# amiketo.net
KiCad netlist of a schematic drawn in EAGLE
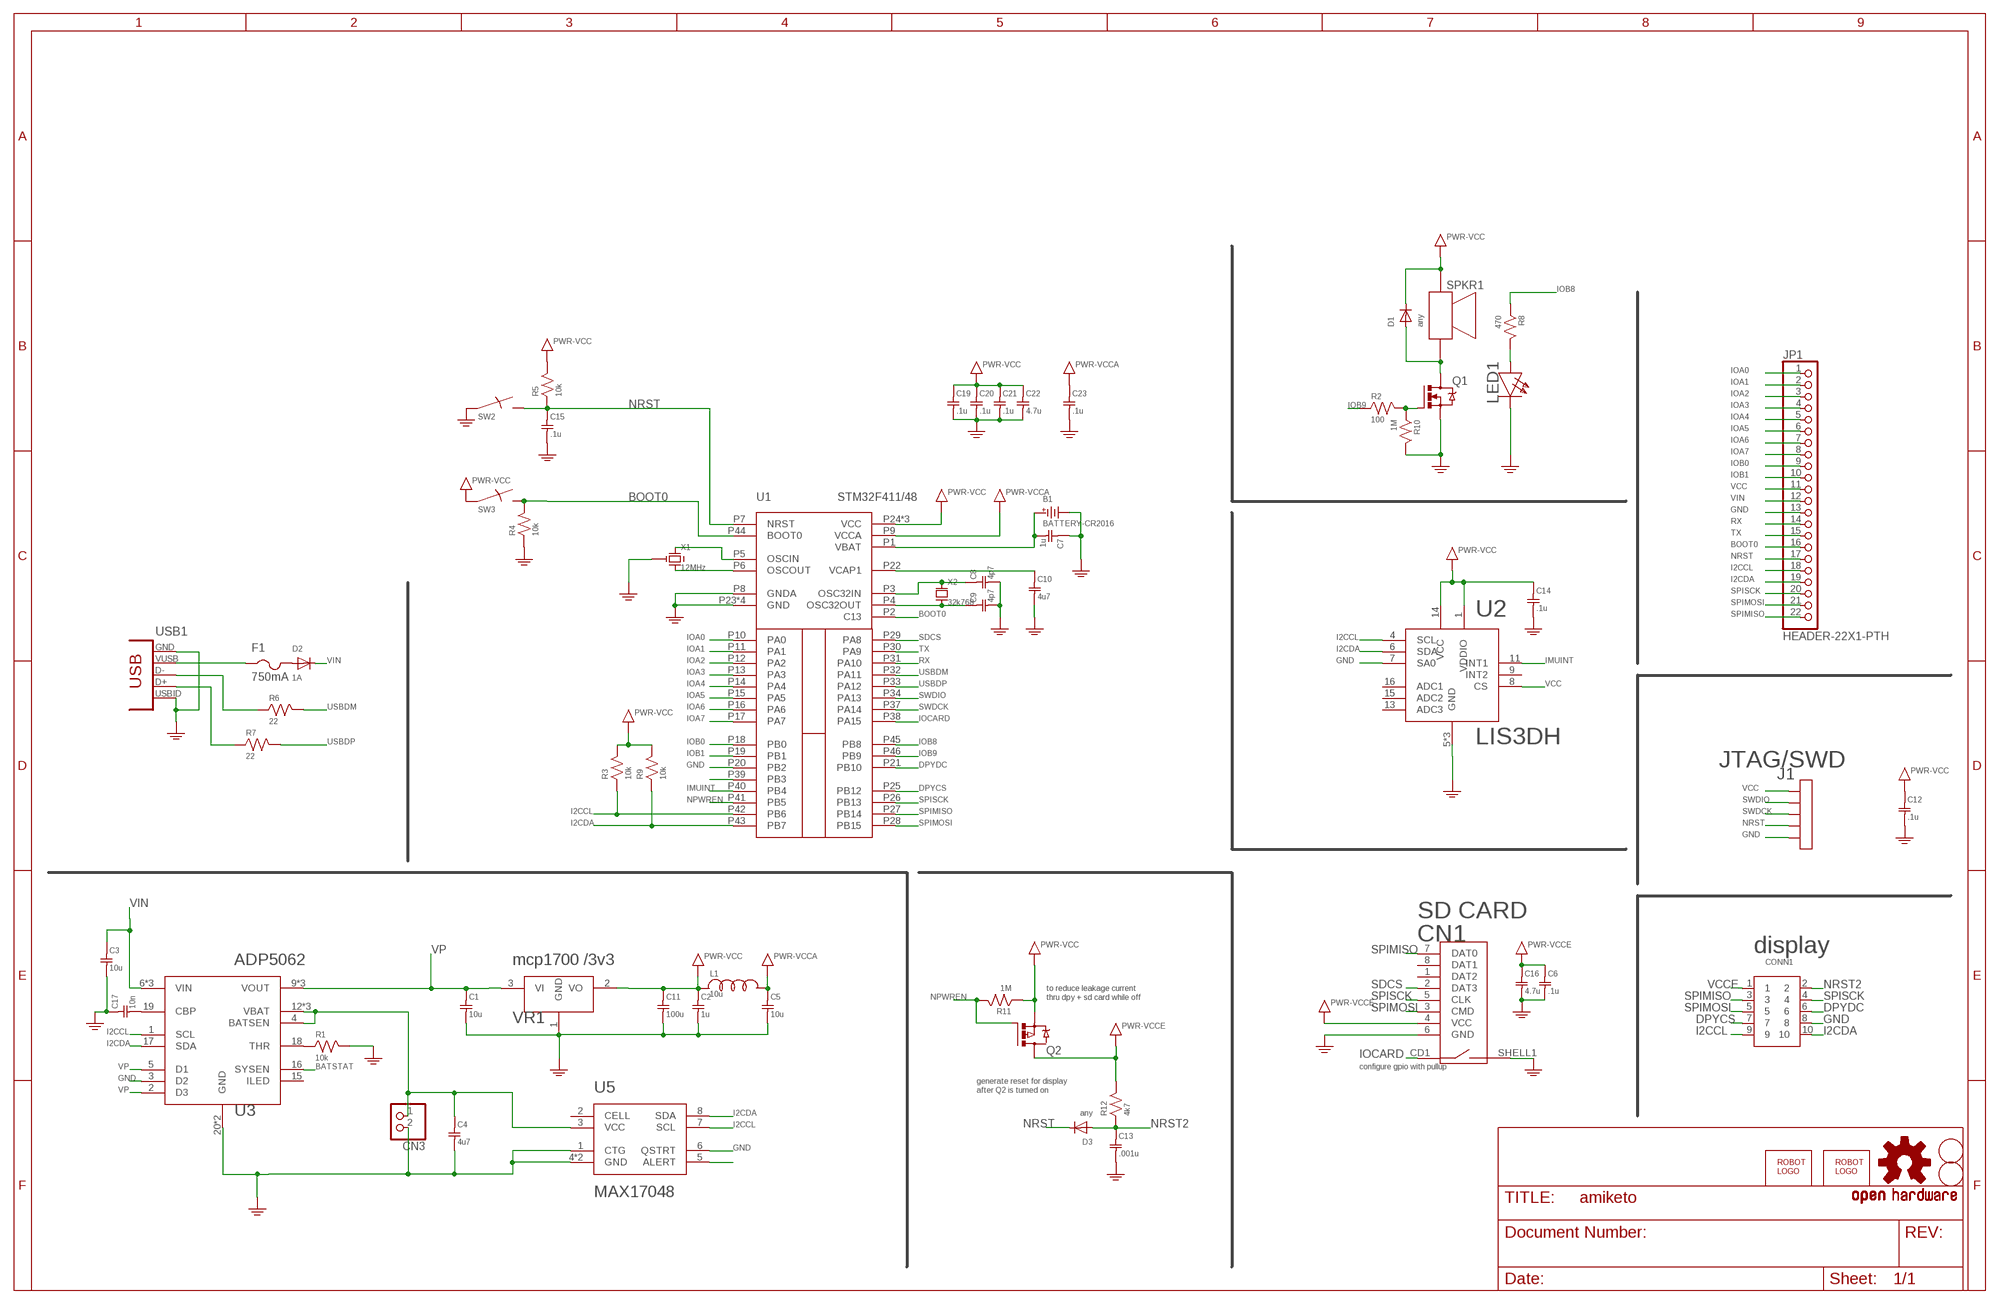
[diagram p0: schematic, sheet 1]

(export (version "E")
  (design (tool "Eeschema 10.0.6"))
  (components
    (comp (ref "B1")
      (value "BATTERY-CR2016")
      (footprint "eagle-import:CR1216")
      (libsource (lib "eagle-import") (part "BATTERY-CR2016"))
    )
    (comp (ref "C1")
      (value "10u")
      (footprint "eagle-import:SMD0603")
      (libsource (lib "eagle-import") (part "C0603"))
    )
    (comp (ref "C2")
      (value "1u")
      (footprint "eagle-import:SMD0603")
      (libsource (lib "eagle-import") (part "C0603"))
    )
    (comp (ref "C3")
      (value "10u")
      (footprint "eagle-import:SMD0603")
      (libsource (lib "eagle-import") (part "C0603"))
    )
    (comp (ref "C4")
      (value "4u7")
      (footprint "eagle-import:SMD0603")
      (libsource (lib "eagle-import") (part "C0603"))
    )
    (comp (ref "C5")
      (value "10u")
      (footprint "eagle-import:SMD0603")
      (libsource (lib "eagle-import") (part "C0603"))
    )
    (comp (ref "C6")
      (value ".1u")
      (footprint "eagle-import:SMD0603")
      (libsource (lib "eagle-import") (part "C0603"))
    )
    (comp (ref "C7")
      (value "1u")
      (footprint "eagle-import:SMD0603")
      (libsource (lib "eagle-import") (part "C0603"))
    )
    (comp (ref "C8")
      (value "4p7")
      (footprint "eagle-import:SMD0603")
      (libsource (lib "eagle-import") (part "C0603"))
    )
    (comp (ref "C9")
      (value "4p7")
      (footprint "eagle-import:SMD0603")
      (libsource (lib "eagle-import") (part "C0603"))
    )
    (comp (ref "C10")
      (value "4u7")
      (footprint "eagle-import:SMD0603")
      (libsource (lib "eagle-import") (part "C0603"))
    )
    (comp (ref "C11")
      (value "100u")
      (footprint "eagle-import:SMD1210")
      (libsource (lib "eagle-import") (part "C1210"))
    )
    (comp (ref "C12")
      (value ".1u")
      (footprint "eagle-import:SMD0603")
      (libsource (lib "eagle-import") (part "C0603"))
    )
    (comp (ref "C13")
      (value ".001u")
      (footprint "eagle-import:SMD0603")
      (libsource (lib "eagle-import") (part "C0603"))
    )
    (comp (ref "C14")
      (value ".1u")
      (footprint "eagle-import:SMD0603")
      (libsource (lib "eagle-import") (part "C0603"))
    )
    (comp (ref "C15")
      (value ".1u")
      (footprint "eagle-import:SMD0603")
      (libsource (lib "eagle-import") (part "C0603"))
    )
    (comp (ref "C16")
      (value "4.7u")
      (footprint "eagle-import:SMD0603")
      (libsource (lib "eagle-import") (part "C0603"))
    )
    (comp (ref "C17")
      (value "10n")
      (footprint "eagle-import:SMD0603")
      (libsource (lib "eagle-import") (part "C0603"))
    )
    (comp (ref "C19")
      (value ".1u")
      (footprint "eagle-import:SMD0603")
      (libsource (lib "eagle-import") (part "C0603"))
    )
    (comp (ref "C20")
      (value ".1u")
      (footprint "eagle-import:SMD0603")
      (libsource (lib "eagle-import") (part "C0603"))
    )
    (comp (ref "C21")
      (value ".1u")
      (footprint "eagle-import:SMD0603")
      (libsource (lib "eagle-import") (part "C0603"))
    )
    (comp (ref "C22")
      (value "4.7u")
      (footprint "eagle-import:SMD0603")
      (libsource (lib "eagle-import") (part "C0603"))
    )
    (comp (ref "C23")
      (value ".1u")
      (footprint "eagle-import:SMD0603")
      (libsource (lib "eagle-import") (part "C0603"))
    )
    (comp (ref "CN1")
      (value "MICROSD-EJECT")
      (footprint "eagle-import:MICROSD_EJECTOR")
      (libsource (lib "eagle-import") (part "MICROSD-EJECT"))
    )
    (comp (ref "CN3")
      (value "JST_2PIN-SMT-RA")
      (footprint "eagle-import:JST-PH-2-SMT-RA")
      (libsource (lib "eagle-import") (part "JST_2PIN-SMT-RA"))
    )
    (comp (ref "CONN1")
      (value "HEADER-5X2-PTH")
      (footprint "eagle-import:HEADER-5X2-PTH")
      (libsource (lib "eagle-import") (part "HEADER-5X2-PTH"))
    )
    (comp (ref "D1")
      (value "any")
      (footprint "eagle-import:SOD-323")
      (libsource (lib "eagle-import") (part "DIODESOD-323"))
    )
    (comp (ref "D2")
      (value "1A")
      (footprint "eagle-import:SMD0805D")
      (libsource (lib "eagle-import") (part "DIODE-0805"))
    )
    (comp (ref "D3")
      (value "any")
      (footprint "eagle-import:SOD-323")
      (libsource (lib "eagle-import") (part "DIODESOD-323"))
    )
    (comp (ref "F1")
      (value "750mA")
      (footprint "eagle-import:SMD1206")
      (libsource (lib "eagle-import") (part "FUSE"))
    )
    (comp (ref "J1")
      (value "HEADER-5X1")
      (footprint "eagle-import:HEADER-5X1-SMD127-NOCR")
      (libsource (lib "eagle-import") (part "HEADER-5X1"))
    )
    (comp (ref "JP1")
      (value "HEADER-22X1-PTH")
      (footprint "eagle-import:HEADER-22X1-PTH")
      (libsource (lib "eagle-import") (part "HEADER-22X1-PTH"))
    )
    (comp (ref "L1")
      (value "10u")
      (footprint "eagle-import:SMD0603")
      (libsource (lib "eagle-import") (part "LSMD0603"))
    )
    (comp (ref "LED1")
      (value "white")
      (footprint "eagle-import:SMD0603D")
      (libsource (lib "eagle-import") (part "LED"))
    )
    (comp (ref "LOGO1")
      (value "OSHW-LOGOM")
      (footprint "eagle-import:OSHW-LOGO-M")
      (libsource (lib "eagle-import") (part "OSHW-LOGOM"))
    )
    (comp (ref "Q1")
      (value "IRLML6344TRPBF")
      (footprint "eagle-import:SOT-23")
      (libsource (lib "eagle-import") (part "MOSFETSOT-23"))
    )
    (comp (ref "Q2")
      (value "DMP2035U-7")
      (footprint "eagle-import:SOT-23")
      (libsource (lib "eagle-import") (part "MOSFET-P"))
    )
    (comp (ref "R1")
      (value "10k")
      (footprint "eagle-import:SMD0603")
      (libsource (lib "eagle-import") (part "R0603"))
    )
    (comp (ref "R2")
      (value "100")
      (footprint "eagle-import:SMD0603")
      (libsource (lib "eagle-import") (part "R0603"))
    )
    (comp (ref "R3")
      (value "10k")
      (footprint "eagle-import:SMD0603")
      (libsource (lib "eagle-import") (part "R0603"))
    )
    (comp (ref "R4")
      (value "10k")
      (footprint "eagle-import:SMD0603")
      (libsource (lib "eagle-import") (part "R0603"))
    )
    (comp (ref "R5")
      (value "10k")
      (footprint "eagle-import:SMD0603")
      (libsource (lib "eagle-import") (part "R0603"))
    )
    (comp (ref "R6")
      (value "22")
      (footprint "eagle-import:SMD0603")
      (libsource (lib "eagle-import") (part "R0603"))
    )
    (comp (ref "R7")
      (value "22")
      (footprint "eagle-import:SMD0603")
      (libsource (lib "eagle-import") (part "R0603"))
    )
    (comp (ref "R8")
      (value "470")
      (footprint "eagle-import:SMD0603")
      (libsource (lib "eagle-import") (part "R0603"))
    )
    (comp (ref "R9")
      (value "10k")
      (footprint "eagle-import:SMD0603")
      (libsource (lib "eagle-import") (part "R0603"))
    )
    (comp (ref "R10")
      (value "1M")
      (footprint "eagle-import:SMD0603")
      (libsource (lib "eagle-import") (part "R0603"))
    )
    (comp (ref "R11")
      (value "1M")
      (footprint "eagle-import:SMD0603")
      (libsource (lib "eagle-import") (part "R0603"))
    )
    (comp (ref "R12")
      (value "4k7")
      (footprint "eagle-import:SMD0603")
      (libsource (lib "eagle-import") (part "R0603"))
    )
    (comp (ref "SPKR1")
      (value "PUI-5040")
      (footprint "eagle-import:PUI-0540")
      (libsource (lib "eagle-import") (part "PUI-5040"))
    )
    (comp (ref "SW2")
      (value "SWITCHKMR211")
      (footprint "eagle-import:KMR211")
      (libsource (lib "eagle-import") (part "SWITCHKMR211"))
    )
    (comp (ref "SW3")
      (value "SWITCHKMR211")
      (footprint "eagle-import:KMR211")
      (libsource (lib "eagle-import") (part "SWITCHKMR211"))
    )
    (comp (ref "U$1")
      (value "ROBOTMAN-LOGO2")
      (footprint "eagle-import:ROBOTMAN-LOGO2")
      (libsource (lib "eagle-import") (part "ROBOTMAN-LOGO2"))
    )
    (comp (ref "U$2")
      (value "FIDUCIAL")
      (footprint "eagle-import:FIDUCIAL_1MM")
      (libsource (lib "eagle-import") (part "FIDUCIAL"))
    )
    (comp (ref "U$3")
      (value "FIDUCIAL")
      (footprint "eagle-import:FIDUCIAL_1MM")
      (libsource (lib "eagle-import") (part "FIDUCIAL"))
    )
    (comp (ref "U$4")
      (value "ROBOTMAN-LOGO2")
      (footprint "eagle-import:ROBOTMAN-LOGO2")
      (libsource (lib "eagle-import") (part "ROBOTMAN-LOGO2"))
    )
    (comp (ref "U1")
      (value "STM32F411/48")
      (footprint "eagle-import:UQPFN48")
      (libsource (lib "eagle-import") (part "STM32F411/48"))
    )
    (comp (ref "U2")
      (value "LIS3DH")
      (footprint "eagle-import:LGA16A")
      (libsource (lib "eagle-import") (part "LIS3DH"))
    )
    (comp (ref "U3")
      (value "ADP5062")
      (footprint "eagle-import:LGA20P")
      (libsource (lib "eagle-import") (part "ADP5062"))
    )
    (comp (ref "U5")
      (value "MAX17048")
      (footprint "eagle-import:TDFN8EP")
      (libsource (lib "eagle-import") (part "MAX17048"))
    )
    (comp (ref "USB1")
      (value "CON-USB-F-MICRO-B")
      (footprint "eagle-import:CONN_USB_MICRO-B")
      (libsource (lib "eagle-import") (part "CON-USB-F-MICRO-B"))
    )
    (comp (ref "VR1")
      (value "mcp1700 /3v3")
      (footprint "eagle-import:SOT-23-3")
      (libsource (lib "eagle-import") (part "REGULATOR-SOT23-3"))
    )
    (comp (ref "X1")
      (value "12MHz")
      (footprint "eagle-import:RESONATOR-CSTCE")
      (libsource (lib "eagle-import") (part "RESONATORCTCE"))
    )
    (comp (ref "X2")
      (value "32k768")
      (footprint "eagle-import:XTAL-32X15")
      (libsource (lib "eagle-import") (part "XTAL32X15"))
    )
  )
  (nets
    (net (code "1") (name "/BATSTAT") (class "Default")
      (node (ref "U3") (pin "16") (pinfunction "SYSEN_16") (pintype "bidirectional"))
    )
    (net (code "2") (name "/BOOT0") (class "Default")
      (node (ref "JP1") (pin "16") (pinfunction "16_16") (pintype "passive"))
      (node (ref "R4") (pin "2") (pinfunction "P$2_2") (pintype "passive"))
      (node (ref "SW3") (pin "2") (pinfunction "P$2_2") (pintype "passive"))
      (node (ref "SW3") (pin "4") (pinfunction "P$2_4") (pintype "passive"))
      (node (ref "U1") (pin "P2") (pinfunction "C13_P2") (pintype "bidirectional"))
      (node (ref "U1") (pin "P44") (pinfunction "BOOT0_P44") (pintype "bidirectional"))
    )
    (net (code "3") (name "/DPYCS") (class "Default")
      (node (ref "CONN1") (pin "7") (pinfunction "7_7") (pintype "passive"))
      (node (ref "U1") (pin "P25") (pinfunction "PB12_P25") (pintype "bidirectional"))
    )
    (net (code "4") (name "/DPYDC") (class "Default")
      (node (ref "CONN1") (pin "6") (pinfunction "6_6") (pintype "passive"))
      (node (ref "U1") (pin "P21") (pinfunction "PB10_P21") (pintype "bidirectional"))
    )
    (net (code "5") (name "/I2CCL") (class "Default")
      (node (ref "CONN1") (pin "9") (pinfunction "9_9") (pintype "passive"))
      (node (ref "JP1") (pin "18") (pinfunction "18_18") (pintype "passive"))
      (node (ref "R3") (pin "1") (pinfunction "P$1_1") (pintype "passive"))
      (node (ref "U1") (pin "P42") (pinfunction "PB6_P42") (pintype "bidirectional"))
      (node (ref "U2") (pin "4") (pinfunction "SCL_4") (pintype "bidirectional"))
      (node (ref "U3") (pin "1") (pinfunction "SCL_1") (pintype "bidirectional"))
      (node (ref "U5") (pin "7") (pinfunction "SCL_7") (pintype "bidirectional"))
    )
    (net (code "6") (name "/I2CDA") (class "Default")
      (node (ref "CONN1") (pin "10") (pinfunction "10_10") (pintype "passive"))
      (node (ref "JP1") (pin "19") (pinfunction "19_19") (pintype "passive"))
      (node (ref "R9") (pin "1") (pinfunction "P$1_1") (pintype "passive"))
      (node (ref "U1") (pin "P43") (pinfunction "PB7_P43") (pintype "bidirectional"))
      (node (ref "U2") (pin "6") (pinfunction "SDA_6") (pintype "bidirectional"))
      (node (ref "U3") (pin "17") (pinfunction "SDA_17") (pintype "bidirectional"))
      (node (ref "U5") (pin "8") (pinfunction "SDA_8") (pintype "bidirectional"))
    )
    (net (code "7") (name "/IMUINT") (class "Default")
      (node (ref "U1") (pin "P40") (pinfunction "PB4_P40") (pintype "bidirectional"))
      (node (ref "U2") (pin "11") (pinfunction "INT1_11") (pintype "bidirectional"))
    )
    (net (code "8") (name "/IOA0") (class "Default")
      (node (ref "JP1") (pin "1") (pinfunction "1_1") (pintype "passive"))
      (node (ref "U1") (pin "P10") (pinfunction "PA0_P10") (pintype "bidirectional"))
    )
    (net (code "9") (name "/IOA1") (class "Default")
      (node (ref "JP1") (pin "2") (pinfunction "2_2") (pintype "passive"))
      (node (ref "U1") (pin "P11") (pinfunction "PA1_P11") (pintype "bidirectional"))
    )
    (net (code "10") (name "/IOA2") (class "Default")
      (node (ref "JP1") (pin "3") (pinfunction "3_3") (pintype "passive"))
      (node (ref "U1") (pin "P12") (pinfunction "PA2_P12") (pintype "bidirectional"))
    )
    (net (code "11") (name "/IOA3") (class "Default")
      (node (ref "JP1") (pin "4") (pinfunction "4_4") (pintype "passive"))
      (node (ref "U1") (pin "P13") (pinfunction "PA3_P13") (pintype "bidirectional"))
    )
    (net (code "12") (name "/IOA4") (class "Default")
      (node (ref "JP1") (pin "5") (pinfunction "5_5") (pintype "passive"))
      (node (ref "U1") (pin "P14") (pinfunction "PA4_P14") (pintype "bidirectional"))
    )
    (net (code "13") (name "/IOA5") (class "Default")
      (node (ref "JP1") (pin "6") (pinfunction "6_6") (pintype "passive"))
      (node (ref "U1") (pin "P15") (pinfunction "PA5_P15") (pintype "bidirectional"))
    )
    (net (code "14") (name "/IOA6") (class "Default")
      (node (ref "JP1") (pin "7") (pinfunction "7_7") (pintype "passive"))
      (node (ref "U1") (pin "P16") (pinfunction "PA6_P16") (pintype "bidirectional"))
    )
    (net (code "15") (name "/IOA7") (class "Default")
      (node (ref "JP1") (pin "8") (pinfunction "8_8") (pintype "passive"))
      (node (ref "U1") (pin "P17") (pinfunction "PA7_P17") (pintype "bidirectional"))
    )
    (net (code "16") (name "/IOB0") (class "Default")
      (node (ref "JP1") (pin "9") (pinfunction "9_9") (pintype "passive"))
      (node (ref "U1") (pin "P18") (pinfunction "PB0_P18") (pintype "bidirectional"))
    )
    (net (code "17") (name "/IOB1") (class "Default")
      (node (ref "JP1") (pin "10") (pinfunction "10_10") (pintype "passive"))
      (node (ref "U1") (pin "P19") (pinfunction "PB1_P19") (pintype "bidirectional"))
    )
    (net (code "18") (name "/IOB8") (class "Default")
      (node (ref "R8") (pin "1") (pinfunction "P$1_1") (pintype "passive"))
      (node (ref "U1") (pin "P45") (pinfunction "PB8_P45") (pintype "bidirectional"))
    )
    (net (code "19") (name "/IOB9") (class "Default")
      (node (ref "R2") (pin "1") (pinfunction "P$1_1") (pintype "passive"))
      (node (ref "U1") (pin "P46") (pinfunction "PB9_P46") (pintype "bidirectional"))
    )
    (net (code "20") (name "/IOCARD") (class "Default")
      (node (ref "CN1") (pin "CD1") (pinfunction "SW1_CD1") (pintype "bidirectional"))
      (node (ref "U1") (pin "P38") (pinfunction "PA15_P38") (pintype "bidirectional"))
    )
    (net (code "21") (name "/NPWREN") (class "Default")
      (node (ref "Q2") (pin "1") (pinfunction "G_1") (pintype "passive"))
      (node (ref "R11") (pin "2") (pinfunction "P$2_2") (pintype "passive"))
      (node (ref "U1") (pin "P41") (pinfunction "PB5_P41") (pintype "bidirectional"))
    )
    (net (code "22") (name "/NRST") (class "Default")
      (node (ref "C15") (pin "1") (pinfunction "P$1_1") (pintype "passive"))
      (node (ref "D3") (pin "C") (pinfunction "C_C") (pintype "passive"))
      (node (ref "J1") (pin "P$4") (pinfunction "4_P$4") (pintype "bidirectional"))
      (node (ref "JP1") (pin "17") (pinfunction "17_17") (pintype "passive"))
      (node (ref "R5") (pin "1") (pinfunction "P$1_1") (pintype "passive"))
      (node (ref "SW2") (pin "2") (pinfunction "P$2_2") (pintype "passive"))
      (node (ref "SW2") (pin "4") (pinfunction "P$2_4") (pintype "passive"))
      (node (ref "U1") (pin "P7") (pinfunction "NRST_P7") (pintype "bidirectional"))
    )
    (net (code "23") (name "/NRST2") (class "Default")
      (node (ref "C13") (pin "1") (pinfunction "P$1_1") (pintype "passive"))
      (node (ref "CONN1") (pin "2") (pinfunction "2_2") (pintype "passive"))
      (node (ref "D3") (pin "A") (pinfunction "A_A") (pintype "passive"))
      (node (ref "R12") (pin "1") (pinfunction "P$1_1") (pintype "passive"))
    )
    (net (code "24") (name "/RX") (class "Default")
      (node (ref "JP1") (pin "14") (pinfunction "14_14") (pintype "passive"))
      (node (ref "U1") (pin "P31") (pinfunction "PA10_P31") (pintype "bidirectional"))
    )
    (net (code "25") (name "/SDCS") (class "Default")
      (node (ref "CN1") (pin "2") (pinfunction "DAT3_2") (pintype "bidirectional"))
      (node (ref "U1") (pin "P29") (pinfunction "PA8_P29") (pintype "bidirectional"))
    )
    (net (code "26") (name "/SPIMISO") (class "Default")
      (node (ref "CN1") (pin "7") (pinfunction "DAT0_7") (pintype "bidirectional"))
      (node (ref "CONN1") (pin "3") (pinfunction "3_3") (pintype "passive"))
      (node (ref "JP1") (pin "22") (pinfunction "22_22") (pintype "passive"))
      (node (ref "U1") (pin "P27") (pinfunction "PB14_P27") (pintype "bidirectional"))
    )
    (net (code "27") (name "/SPIMOSI") (class "Default")
      (node (ref "CN1") (pin "3") (pinfunction "CMD_3") (pintype "bidirectional"))
      (node (ref "CONN1") (pin "5") (pinfunction "5_5") (pintype "passive"))
      (node (ref "JP1") (pin "21") (pinfunction "21_21") (pintype "passive"))
      (node (ref "U1") (pin "P28") (pinfunction "PB15_P28") (pintype "bidirectional"))
    )
    (net (code "28") (name "/SPISCK") (class "Default")
      (node (ref "CN1") (pin "5") (pinfunction "CLK_5") (pintype "bidirectional"))
      (node (ref "CONN1") (pin "4") (pinfunction "4_4") (pintype "passive"))
      (node (ref "JP1") (pin "20") (pinfunction "20_20") (pintype "passive"))
      (node (ref "U1") (pin "P26") (pinfunction "PB13_P26") (pintype "bidirectional"))
    )
    (net (code "29") (name "/SWDCK") (class "Default")
      (node (ref "J1") (pin "P$3") (pinfunction "3_P$3") (pintype "bidirectional"))
      (node (ref "U1") (pin "P37") (pinfunction "PA14_P37") (pintype "bidirectional"))
    )
    (net (code "30") (name "/SWDIO") (class "Default")
      (node (ref "J1") (pin "P$2") (pinfunction "2_P$2") (pintype "bidirectional"))
      (node (ref "U1") (pin "P34") (pinfunction "PA13_P34") (pintype "bidirectional"))
    )
    (net (code "31") (name "/TX") (class "Default")
      (node (ref "JP1") (pin "15") (pinfunction "15_15") (pintype "passive"))
      (node (ref "U1") (pin "P30") (pinfunction "PA9_P30") (pintype "bidirectional"))
    )
    (net (code "32") (name "/USBDM") (class "Default")
      (node (ref "R6") (pin "2") (pinfunction "P$2_2") (pintype "passive"))
      (node (ref "U1") (pin "P32") (pinfunction "PA11_P32") (pintype "bidirectional"))
    )
    (net (code "33") (name "/USBDP") (class "Default")
      (node (ref "R7") (pin "2") (pinfunction "P$2_2") (pintype "passive"))
      (node (ref "U1") (pin "P33") (pinfunction "PA12_P33") (pintype "bidirectional"))
    )
    (net (code "34") (name "/VIN") (class "Default")
      (node (ref "C3") (pin "1") (pinfunction "P$1_1") (pintype "passive"))
      (node (ref "D2") (pin "C") (pinfunction "C_C") (pintype "passive"))
      (node (ref "JP1") (pin "12") (pinfunction "12_12") (pintype "passive"))
      (node (ref "U3") (pin "6") (pinfunction "VIN_6") (pintype "bidirectional"))
      (node (ref "U3") (pin "7") (pinfunction "VIN_7") (pintype "bidirectional"))
      (node (ref "U3") (pin "8") (pinfunction "VIN_8") (pintype "bidirectional"))
    )
    (net (code "35") (name "/VP") (class "Default")
      (node (ref "C1") (pin "1") (pinfunction "P$1_1") (pintype "passive"))
      (node (ref "U3") (pin "10") (pinfunction "VOUT_10") (pintype "bidirectional"))
      (node (ref "U3") (pin "11") (pinfunction "VOUT_11") (pintype "bidirectional"))
      (node (ref "U3") (pin "2") (pinfunction "D3_2") (pintype "bidirectional"))
      (node (ref "U3") (pin "5") (pinfunction "D1_5") (pintype "bidirectional"))
      (node (ref "U3") (pin "9") (pinfunction "VOUT_9") (pintype "bidirectional"))
      (node (ref "VR1") (pin "3") (pinfunction "VI_3") (pintype "bidirectional"))
    )
    (net (code "36") (name "Net-(C4-P$1)") (class "Default")
      (node (ref "C4") (pin "1") (pinfunction "P$1_1") (pintype "passive"))
      (node (ref "CN3") (pin "1") (pinfunction "2_1") (pintype "passive"))
      (node (ref "U3") (pin "12") (pinfunction "VBAT_12") (pintype "bidirectional"))
      (node (ref "U3") (pin "13") (pinfunction "VBAT_13") (pintype "bidirectional"))
      (node (ref "U3") (pin "14") (pinfunction "VBAT_14") (pintype "bidirectional"))
      (node (ref "U3") (pin "4") (pinfunction "BATSEN_4") (pintype "bidirectional"))
      (node (ref "U5") (pin "3") (pinfunction "VCC_3") (pintype "bidirectional"))
    )
    (net (code "37") (name "Net-(C7-P$2)") (class "Default")
      (node (ref "B1") (pin "PLUS1") (pinfunction "P_PLUS1") (pintype "bidirectional"))
      (node (ref "B1") (pin "PLUS2") (pinfunction "P_PLUS2") (pintype "bidirectional"))
      (node (ref "C7") (pin "2") (pinfunction "P$2_2") (pintype "passive"))
      (node (ref "U1") (pin "P1") (pinfunction "VBAT_P1") (pintype "bidirectional"))
    )
    (net (code "38") (name "Net-(C8-P$1)") (class "Default")
      (node (ref "C8") (pin "1") (pinfunction "P$1_1") (pintype "passive"))
      (node (ref "U1") (pin "P3") (pinfunction "OSC32IN_P3") (pintype "bidirectional"))
      (node (ref "X2") (pin "P$1") (pinfunction "P$1_P$1") (pintype "passive"))
    )
    (net (code "39") (name "Net-(C9-P$1)") (class "Default")
      (node (ref "C9") (pin "1") (pinfunction "P$1_1") (pintype "passive"))
      (node (ref "U1") (pin "P4") (pinfunction "OSC32OUT_P4") (pintype "bidirectional"))
      (node (ref "X2") (pin "P$2") (pinfunction "P$2_P$2") (pintype "passive"))
    )
    (net (code "40") (name "Net-(C10-P$1)") (class "Default")
      (node (ref "C10") (pin "1") (pinfunction "P$1_1") (pintype "passive"))
      (node (ref "U1") (pin "P22") (pinfunction "VCAP1_P22") (pintype "bidirectional"))
    )
    (net (code "41") (name "Net-(C17-P$2)") (class "Default")
      (node (ref "C17") (pin "2") (pinfunction "P$2_2") (pintype "passive"))
      (node (ref "U3") (pin "19") (pinfunction "CBP_19") (pintype "bidirectional"))
    )
    (net (code "42") (name "Net-(D2-PadA)") (class "Default")
      (node (ref "D2") (pin "A") (pinfunction "A_A") (pintype "passive"))
      (node (ref "F1") (pin "2") (pinfunction "2_2") (pintype "passive"))
    )
    (net (code "43") (name "Net-(Q1-D)") (class "Default")
      (node (ref "D1") (pin "A") (pinfunction "A_A") (pintype "passive"))
      (node (ref "Q1") (pin "3") (pinfunction "D_3") (pintype "passive"))
      (node (ref "SPKR1") (pin "P2") (pinfunction "P2_P2") (pintype "input"))
    )
    (net (code "44") (name "Net-(Q1-G)") (class "Default")
      (node (ref "Q1") (pin "1") (pinfunction "G_1") (pintype "passive"))
      (node (ref "R10") (pin "1") (pinfunction "P$1_1") (pintype "passive"))
      (node (ref "R2") (pin "2") (pinfunction "P$2_2") (pintype "passive"))
    )
    (net (code "45") (name "Net-(R1-P$1)") (class "Default")
      (node (ref "R1") (pin "1") (pinfunction "P$1_1") (pintype "passive"))
      (node (ref "U3") (pin "18") (pinfunction "THR_18") (pintype "bidirectional"))
    )
    (net (code "46") (name "Net-(R6-P$1)") (class "Default")
      (node (ref "R6") (pin "1") (pinfunction "P$1_1") (pintype "passive"))
      (node (ref "USB1") (pin "P2") (pinfunction "D-_P2") (pintype "bidirectional"))
    )
    (net (code "47") (name "Net-(R7-P$1)") (class "Default")
      (node (ref "R7") (pin "1") (pinfunction "P$1_1") (pintype "passive"))
      (node (ref "USB1") (pin "P3") (pinfunction "D+_P3") (pintype "bidirectional"))
    )
    (net (code "48") (name "Net-(R8-P$2)") (class "Default")
      (node (ref "LED1") (pin "A") (pinfunction "A_A") (pintype "passive"))
      (node (ref "R8") (pin "2") (pinfunction "P$2_2") (pintype "passive"))
    )
    (net (code "49") (name "Net-(U1-OSCIN)") (class "Default")
      (node (ref "U1") (pin "P5") (pinfunction "OSCIN_P5") (pintype "bidirectional"))
      (node (ref "X1") (pin "1") (pinfunction "X1_1") (pintype "passive"))
    )
    (net (code "50") (name "Net-(U1-OSCOUT)") (class "Default")
      (node (ref "U1") (pin "P6") (pinfunction "OSCOUT_P6") (pintype "bidirectional"))
      (node (ref "X1") (pin "3") (pinfunction "X2_3") (pintype "passive"))
    )
    (net (code "51") (name "Net-(USB1B-VUSB)") (class "Default")
      (node (ref "F1") (pin "1") (pinfunction "1_1") (pintype "passive"))
      (node (ref "USB1") (pin "P1") (pinfunction "VUSB_P1") (pintype "bidirectional"))
    )
    (net (code "52") (name "PWR-GND") (class "Default")
      (node (ref "B1") (pin "MINUS") (pinfunction "M_MINUS") (pintype "bidirectional"))
      (node (ref "C1") (pin "2") (pinfunction "P$2_2") (pintype "passive"))
      (node (ref "C10") (pin "2") (pinfunction "P$2_2") (pintype "passive"))
      (node (ref "C11") (pin "2") (pinfunction "P$2_2") (pintype "passive"))
      (node (ref "C12") (pin "2") (pinfunction "P$2_2") (pintype "passive"))
      (node (ref "C13") (pin "2") (pinfunction "P$2_2") (pintype "passive"))
      (node (ref "C14") (pin "2") (pinfunction "P$2_2") (pintype "passive"))
      (node (ref "C15") (pin "2") (pinfunction "P$2_2") (pintype "passive"))
      (node (ref "C16") (pin "2") (pinfunction "P$2_2") (pintype "passive"))
      (node (ref "C17") (pin "1") (pinfunction "P$1_1") (pintype "passive"))
      (node (ref "C19") (pin "2") (pinfunction "P$2_2") (pintype "passive"))
      (node (ref "C2") (pin "2") (pinfunction "P$2_2") (pintype "passive"))
      (node (ref "C20") (pin "2") (pinfunction "P$2_2") (pintype "passive"))
      (node (ref "C21") (pin "2") (pinfunction "P$2_2") (pintype "passive"))
      (node (ref "C22") (pin "2") (pinfunction "P$2_2") (pintype "passive"))
      (node (ref "C23") (pin "2") (pinfunction "P$2_2") (pintype "passive"))
      (node (ref "C3") (pin "2") (pinfunction "P$2_2") (pintype "passive"))
      (node (ref "C4") (pin "2") (pinfunction "P$2_2") (pintype "passive"))
      (node (ref "C5") (pin "2") (pinfunction "P$2_2") (pintype "passive"))
      (node (ref "C6") (pin "2") (pinfunction "P$2_2") (pintype "passive"))
      (node (ref "C7") (pin "1") (pinfunction "P$1_1") (pintype "passive"))
      (node (ref "C8") (pin "2") (pinfunction "P$2_2") (pintype "passive"))
      (node (ref "C9") (pin "2") (pinfunction "P$2_2") (pintype "passive"))
      (node (ref "CN1") (pin "6") (pinfunction "GND_6") (pintype "bidirectional"))
      (node (ref "CN1") (pin "SHELL1") (pinfunction "SW2_SHELL1") (pintype "bidirectional"))
      (node (ref "CN3") (pin "2") (pinfunction "1_2") (pintype "passive"))
      (node (ref "CONN1") (pin "8") (pinfunction "8_8") (pintype "passive"))
      (node (ref "J1") (pin "P$5") (pinfunction "5_P$5") (pintype "bidirectional"))
      (node (ref "JP1") (pin "13") (pinfunction "13_13") (pintype "passive"))
      (node (ref "LED1") (pin "C") (pinfunction "C_C") (pintype "passive"))
      (node (ref "Q1") (pin "2") (pinfunction "S_2") (pintype "passive"))
      (node (ref "R1") (pin "2") (pinfunction "P$2_2") (pintype "passive"))
      (node (ref "R10") (pin "2") (pinfunction "P$2_2") (pintype "passive"))
      (node (ref "R4") (pin "1") (pinfunction "P$1_1") (pintype "passive"))
      (node (ref "SW2") (pin "1") (pinfunction "P$1_1") (pintype "passive"))
      (node (ref "SW2") (pin "3") (pinfunction "P$1_3") (pintype "passive"))
      (node (ref "U1") (pin "P20") (pinfunction "PB2_P20") (pintype "bidirectional"))
      (node (ref "U1") (pin "P23") (pinfunction "GND_P23") (pintype "bidirectional"))
      (node (ref "U1") (pin "P35") (pinfunction "GND_P35") (pintype "bidirectional"))
      (node (ref "U1") (pin "P47") (pinfunction "GND_P47") (pintype "bidirectional"))
      (node (ref "U1") (pin "P8") (pinfunction "GNDA_P8") (pintype "bidirectional"))
      (node (ref "U1") (pin "PAD") (pinfunction "GND_PAD") (pintype "bidirectional"))
      (node (ref "U2") (pin "10") (pinfunction "GND_10") (pintype "power_in"))
      (node (ref "U2") (pin "12") (pinfunction "GND_12") (pintype "power_in"))
      (node (ref "U2") (pin "5") (pinfunction "GND_5") (pintype "power_in"))
      (node (ref "U2") (pin "7") (pinfunction "SA0_7") (pintype "bidirectional"))
      (node (ref "U3") (pin "20") (pinfunction "GND_20") (pintype "bidirectional"))
      (node (ref "U3") (pin "3") (pinfunction "D2_3") (pintype "bidirectional"))
      (node (ref "U3") (pin "PAD") (pinfunction "GND_PAD") (pintype "bidirectional"))
      (node (ref "U5") (pin "1") (pinfunction "CTG_1") (pintype "bidirectional"))
      (node (ref "U5") (pin "4") (pinfunction "GND_4") (pintype "bidirectional"))
      (node (ref "U5") (pin "6") (pinfunction "QSTRT_6") (pintype "bidirectional"))
      (node (ref "U5") (pin "PAD") (pinfunction "GND_PAD") (pintype "bidirectional"))
      (node (ref "USB1") (pin "P4") (pinfunction "USBID_P4") (pintype "bidirectional"))
      (node (ref "USB1") (pin "P5") (pinfunction "GND_P5") (pintype "bidirectional"))
      (node (ref "VR1") (pin "1") (pinfunction "GND_1") (pintype "bidirectional"))
      (node (ref "X1") (pin "2") (pinfunction "G_2") (pintype "input"))
    )
    (net (code "53") (name "PWR-VCC") (class "Default")
      (node (ref "C11") (pin "1") (pinfunction "P$1_1") (pintype "passive"))
      (node (ref "C12") (pin "1") (pinfunction "P$1_1") (pintype "passive"))
      (node (ref "C14") (pin "1") (pinfunction "P$1_1") (pintype "passive"))
      (node (ref "C19") (pin "1") (pinfunction "P$1_1") (pintype "passive"))
      (node (ref "C2") (pin "1") (pinfunction "P$1_1") (pintype "passive"))
      (node (ref "C20") (pin "1") (pinfunction "P$1_1") (pintype "passive"))
      (node (ref "C21") (pin "1") (pinfunction "P$1_1") (pintype "passive"))
      (node (ref "C22") (pin "1") (pinfunction "P$1_1") (pintype "passive"))
      (node (ref "D1") (pin "C") (pinfunction "C_C") (pintype "passive"))
      (node (ref "J1") (pin "P$1") (pinfunction "1_P$1") (pintype "bidirectional"))
      (node (ref "JP1") (pin "11") (pinfunction "11_11") (pintype "passive"))
      (node (ref "L1") (pin "1") (pinfunction "P$1_1") (pintype "passive"))
      (node (ref "Q2") (pin "2") (pinfunction "S_2") (pintype "passive"))
      (node (ref "R11") (pin "1") (pinfunction "P$1_1") (pintype "passive"))
      (node (ref "R3") (pin "2") (pinfunction "P$2_2") (pintype "passive"))
      (node (ref "R5") (pin "2") (pinfunction "P$2_2") (pintype "passive"))
      (node (ref "R9") (pin "2") (pinfunction "P$2_2") (pintype "passive"))
      (node (ref "SPKR1") (pin "P1") (pinfunction "P1_P1") (pintype "input"))
      (node (ref "SW3") (pin "1") (pinfunction "P$1_1") (pintype "passive"))
      (node (ref "SW3") (pin "3") (pinfunction "P$1_3") (pintype "passive"))
      (node (ref "U1") (pin "P24") (pinfunction "VCC_P24") (pintype "bidirectional"))
      (node (ref "U1") (pin "P36") (pinfunction "VCC_P36") (pintype "bidirectional"))
      (node (ref "U1") (pin "P48") (pinfunction "VCC_P48") (pintype "bidirectional"))
      (node (ref "U2") (pin "1") (pinfunction "VDDIO_1") (pintype "bidirectional"))
      (node (ref "U2") (pin "14") (pinfunction "VCC_14") (pintype "power_in"))
      (node (ref "U2") (pin "8") (pinfunction "CS_8") (pintype "bidirectional"))
      (node (ref "VR1") (pin "2") (pinfunction "VO_2") (pintype "bidirectional"))
    )
    (net (code "54") (name "PWR-VCCA") (class "Default")
      (node (ref "C23") (pin "1") (pinfunction "P$1_1") (pintype "passive"))
      (node (ref "C5") (pin "1") (pinfunction "P$1_1") (pintype "passive"))
      (node (ref "L1") (pin "2") (pinfunction "P$2_2") (pintype "passive"))
      (node (ref "U1") (pin "P9") (pinfunction "VCCA_P9") (pintype "bidirectional"))
    )
    (net (code "55") (name "PWR-VCCE") (class "Default")
      (node (ref "C16") (pin "1") (pinfunction "P$1_1") (pintype "passive"))
      (node (ref "C6") (pin "1") (pinfunction "P$1_1") (pintype "passive"))
      (node (ref "CN1") (pin "4") (pinfunction "VCC_4") (pintype "bidirectional"))
      (node (ref "CONN1") (pin "1") (pinfunction "1_1") (pintype "passive"))
      (node (ref "Q2") (pin "3") (pinfunction "D_3") (pintype "passive"))
      (node (ref "R12") (pin "2") (pinfunction "P$2_2") (pintype "passive"))
    )
    (net (code "56") (name "unconnected-(CN1-DAT1-Pad8)") (class "Default")
      (node (ref "CN1") (pin "8") (pinfunction "DAT1_8") (pintype "bidirectional"))
    )
    (net (code "57") (name "unconnected-(CN1-DAT2-Pad1)") (class "Default")
      (node (ref "CN1") (pin "1") (pinfunction "DAT2_1") (pintype "bidirectional"))
    )
    (net (code "58") (name "unconnected-(U1-PB3-PadP39)") (class "Default")
      (node (ref "U1") (pin "P39") (pinfunction "PB3_P39") (pintype "bidirectional"))
    )
    (net (code "59") (name "unconnected-(U2-ADC1-Pad16)") (class "Default")
      (node (ref "U2") (pin "16") (pinfunction "ADC1_16") (pintype "bidirectional"))
    )
    (net (code "60") (name "unconnected-(U2-ADC2-Pad15)") (class "Default")
      (node (ref "U2") (pin "15") (pinfunction "ADC2_15") (pintype "bidirectional"))
    )
    (net (code "61") (name "unconnected-(U2-ADC3-Pad13)") (class "Default")
      (node (ref "U2") (pin "13") (pinfunction "ADC3_13") (pintype "bidirectional"))
    )
    (net (code "62") (name "unconnected-(U2-INT2-Pad9)") (class "Default")
      (node (ref "U2") (pin "9") (pinfunction "INT2_9") (pintype "bidirectional"))
    )
    (net (code "63") (name "unconnected-(U3-ILED-Pad15)") (class "Default")
      (node (ref "U3") (pin "15") (pinfunction "ILED_15") (pintype "bidirectional"))
    )
    (net (code "64") (name "unconnected-(U5-ALERT-Pad5)") (class "Default")
      (node (ref "U5") (pin "5") (pinfunction "ALERT_5") (pintype "bidirectional"))
    )
    (net (code "65") (name "unconnected-(U5-CELL-Pad2)") (class "Default")
      (node (ref "U5") (pin "2") (pinfunction "CELL_2") (pintype "bidirectional"))
    )
  )
)
